# YYB-Sheet1.net
KiCad netlist of a schematic drawn in Altium Designer
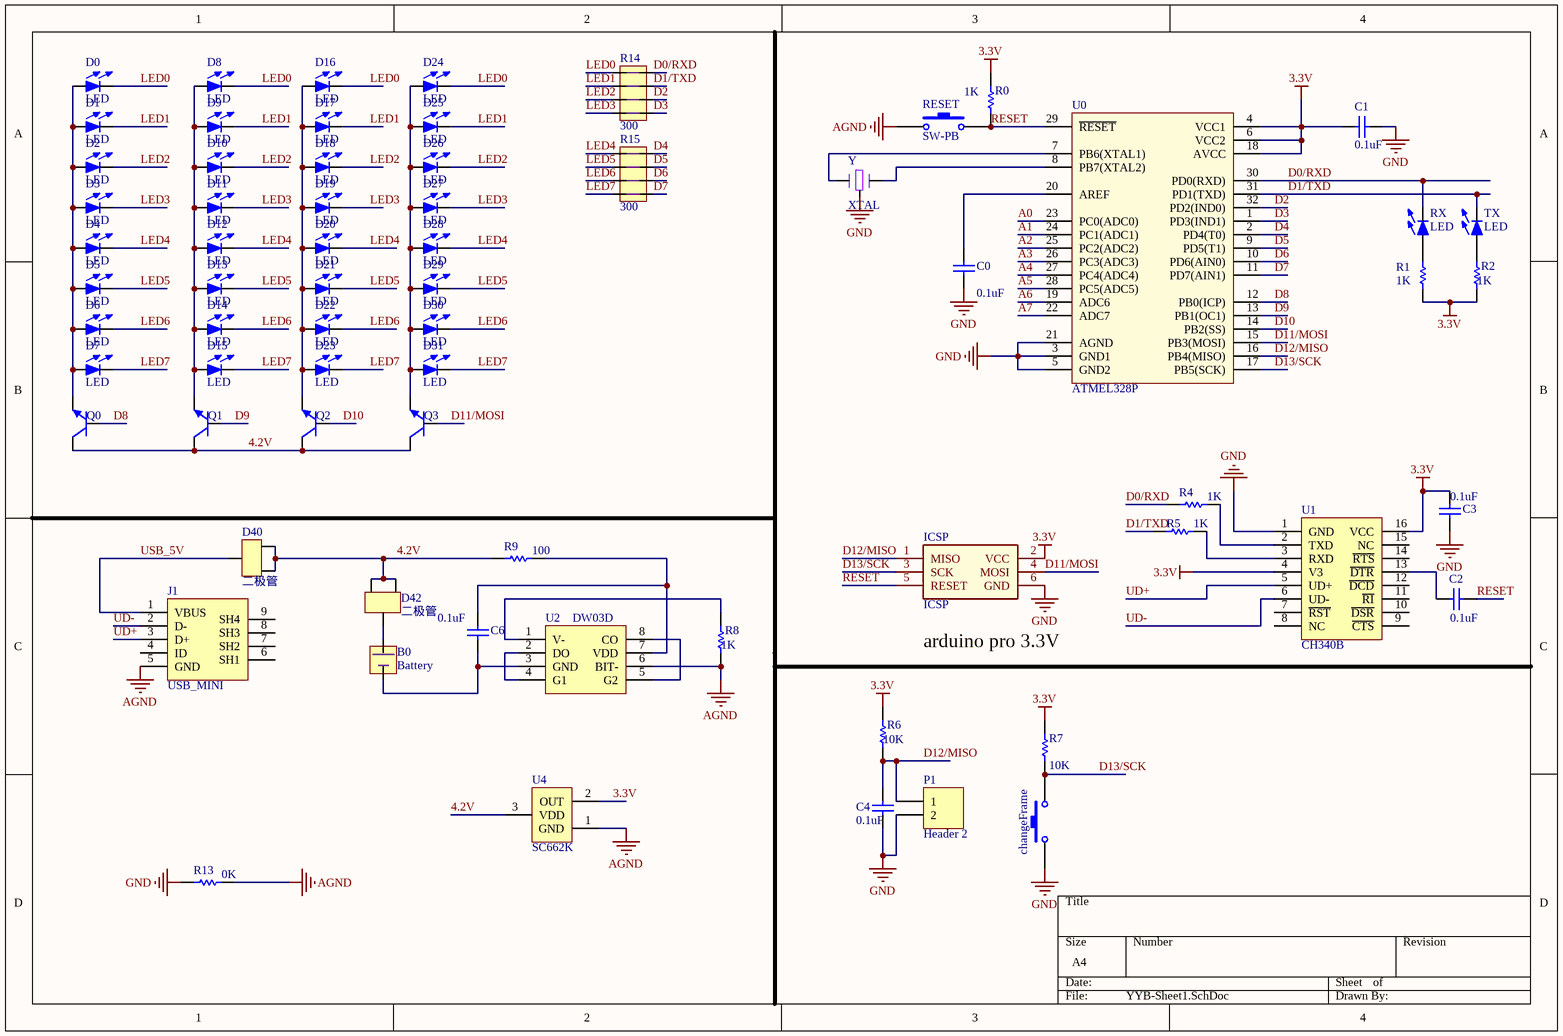
[diagram p0: YYB-Sheet1.SchDoc]

(export (version "E")
  (design (tool "Eeschema 10.0.6"))
  (components
    (comp (ref "B0") (value "Battery") (footprint "LI") (libsource (lib "aistlab") (part "Battery")))
    (comp (ref "C0")
      (value "0.1uF")
      (footprint "6-0805_N")
      (description "Capacitor")
      (fields (field (name "PUBLISHER") "Altium Limited"))
      (libsource (lib "Miscellaneous Devices") (part "Cap"))
    )
    (comp (ref "C1")
      (value "0.1uF")
      (footprint "6-0805_N")
      (description "Capacitor")
      (fields (field (name "Comment") "Cap") (field (name "PUBLISHER") "Altium Limited"))
      (libsource (lib "Miscellaneous Devices") (part "Cap"))
    )
    (comp (ref "C2")
      (value "0.1uF")
      (footprint "6-0805_N")
      (description "Capacitor")
      (fields (field (name "Comment") "Cap") (field (name "PUBLISHER") "Altium Limited"))
      (libsource (lib "Miscellaneous Devices") (part "Cap"))
    )
    (comp (ref "C3")
      (value "0.1uF")
      (footprint "6-0805_N")
      (description "Capacitor")
      (fields (field (name "Comment") "Cap") (field (name "PUBLISHER") "Altium Limited"))
      (libsource (lib "Miscellaneous Devices") (part "Cap"))
    )
    (comp (ref "C4")
      (value "0.1uF")
      (footprint "6-0805_N")
      (description "Capacitor")
      (fields (field (name "Comment") "Cap") (field (name "PUBLISHER") "Altium Limited"))
      (libsource (lib "Miscellaneous Devices") (part "Cap"))
    )
    (comp (ref "C6")
      (value "0.1uF")
      (footprint "6-0805_N")
      (description "Capacitor")
      (fields (field (name "Comment") "Cap") (field (name "PUBLISHER") "Altium Limited"))
      (libsource (lib "Miscellaneous Devices") (part "Cap"))
    )
    (comp (ref "changeFrame")
      (value "SW-PB")
      (footprint "KEY_SODFL_2-Leads")
      (description "Switch")
      (fields (field (name "PUBLISHER") "Altium Limited"))
      (libsource (lib "Miscellaneous Devices") (part "SW-PB"))
    )
    (comp (ref "D0") (value "LED") (footprint "LED_0805") (libsource (lib "aistlab") (part "LED")))
    (comp (ref "D1") (value "LED") (footprint "LED_0805") (libsource (lib "aistlab") (part "LED")))
    (comp (ref "D2") (value "LED") (footprint "LED_0805") (libsource (lib "aistlab") (part "LED")))
    (comp (ref "D3") (value "LED") (footprint "LED_0805") (libsource (lib "aistlab") (part "LED")))
    (comp (ref "D4") (value "LED") (footprint "LED_0805") (libsource (lib "aistlab") (part "LED")))
    (comp (ref "D5") (value "LED") (footprint "LED_0805") (libsource (lib "aistlab") (part "LED")))
    (comp (ref "D6") (value "LED") (footprint "LED_0805") (libsource (lib "aistlab") (part "LED")))
    (comp (ref "D7") (value "LED") (footprint "LED_0805") (libsource (lib "aistlab") (part "LED")))
    (comp (ref "D8") (value "LED") (footprint "LED_0805") (libsource (lib "aistlab") (part "LED")))
    (comp (ref "D9") (value "LED") (footprint "LED_0805") (libsource (lib "aistlab") (part "LED")))
    (comp (ref "D10") (value "LED") (footprint "LED_0805") (libsource (lib "aistlab") (part "LED")))
    (comp (ref "D11") (value "LED") (footprint "LED_0805") (libsource (lib "aistlab") (part "LED")))
    (comp (ref "D12") (value "LED") (footprint "LED_0805") (libsource (lib "aistlab") (part "LED")))
    (comp (ref "D13") (value "LED") (footprint "LED_0805") (libsource (lib "aistlab") (part "LED")))
    (comp (ref "D14") (value "LED") (footprint "LED_0805") (libsource (lib "aistlab") (part "LED")))
    (comp (ref "D15") (value "LED") (footprint "LED_0805") (libsource (lib "aistlab") (part "LED")))
    (comp (ref "D16") (value "LED") (footprint "LED_0805") (libsource (lib "aistlab") (part "LED")))
    (comp (ref "D17") (value "LED") (footprint "LED_0805") (libsource (lib "aistlab") (part "LED")))
    (comp (ref "D18") (value "LED") (footprint "LED_0805") (libsource (lib "aistlab") (part "LED")))
    (comp (ref "D19") (value "LED") (footprint "LED_0805") (libsource (lib "aistlab") (part "LED")))
    (comp (ref "D20") (value "LED") (footprint "LED_0805") (libsource (lib "aistlab") (part "LED")))
    (comp (ref "D21") (value "LED") (footprint "LED_0805") (libsource (lib "aistlab") (part "LED")))
    (comp (ref "D22") (value "LED") (footprint "LED_0805") (libsource (lib "aistlab") (part "LED")))
    (comp (ref "D23") (value "LED") (footprint "LED_0805") (libsource (lib "aistlab") (part "LED")))
    (comp (ref "D24") (value "LED") (footprint "LED_0805") (libsource (lib "aistlab") (part "LED")))
    (comp (ref "D25") (value "LED") (footprint "LED_0805") (libsource (lib "aistlab") (part "LED")))
    (comp (ref "D26") (value "LED") (footprint "LED_0805") (libsource (lib "aistlab") (part "LED")))
    (comp (ref "D27") (value "LED") (footprint "LED_0805") (libsource (lib "aistlab") (part "LED")))
    (comp (ref "D28") (value "LED") (footprint "LED_0805") (libsource (lib "aistlab") (part "LED")))
    (comp (ref "D29") (value "LED") (footprint "LED_0805") (libsource (lib "aistlab") (part "LED")))
    (comp (ref "D30") (value "LED") (footprint "LED_0805") (libsource (lib "aistlab") (part "LED")))
    (comp (ref "D31") (value "LED") (footprint "LED_0805") (libsource (lib "aistlab") (part "LED")))
    (comp (ref "D40") (value "二极管") (footprint "SOT-23") (libsource (lib "aistlab") (part "二极管")))
    (comp (ref "D42") (value "二极管") (footprint "SOT-23") (libsource (lib "") (part "二极管_1")))
    (comp (ref "ICSP") (value "ICSP") (footprint "DIP6") (libsource (lib "aistlab") (part "ICSP")))
    (comp (ref "J1")
      (value "USB_MINI")
      (footprint "MICRO_USB")
      (libsource (lib "YYB-Schlib1") (part "USB_MINI"))
    )
    (comp (ref "P1")
      (value "Header 2")
      (footprint "HDR1X2")
      (description "Header, 2-Pin")
      (fields (field (name "PUBLISHER") "Altium Limited"))
      (libsource (lib "Miscellaneous Connectors") (part "Header 2"))
    )
    (comp (ref "Q0")
      (value "transistor")
      (footprint "SOT-23")
      (libsource (lib "aistlab") (part "transistor"))
    )
    (comp (ref "Q1")
      (value "transistor")
      (footprint "SOT-23")
      (libsource (lib "aistlab") (part "transistor"))
    )
    (comp (ref "Q2")
      (value "transistor")
      (footprint "SOT-23")
      (libsource (lib "aistlab") (part "transistor"))
    )
    (comp (ref "Q3")
      (value "transistor")
      (footprint "SOT-23")
      (libsource (lib "aistlab") (part "transistor"))
    )
    (comp (ref "R0")
      (value "1K")
      (footprint "6-0805_N")
      (description "Resistor")
      (fields (field (name "PUBLISHER") "Altium Limited"))
      (libsource (lib "Miscellaneous Devices") (part "Res1"))
    )
    (comp (ref "R1")
      (value "1K")
      (footprint "6-0805_N")
      (description "Resistor")
      (fields (field (name "Comment") "Res1") (field (name "PUBLISHER") "Altium Limited"))
      (libsource (lib "Miscellaneous Devices") (part "Res1"))
    )
    (comp (ref "R2")
      (value "1K")
      (footprint "6-0805_N")
      (description "Resistor")
      (fields (field (name "Comment") "Res1") (field (name "PUBLISHER") "Altium Limited"))
      (libsource (lib "Miscellaneous Devices") (part "Res1"))
    )
    (comp (ref "R4")
      (value "1K")
      (footprint "6-0805_N")
      (description "Resistor")
      (fields (field (name "Comment") "Res1") (field (name "PUBLISHER") "Altium Limited"))
      (libsource (lib "Miscellaneous Devices") (part "Res1"))
    )
    (comp (ref "R5")
      (value "1K")
      (footprint "6-0805_N")
      (description "Resistor")
      (fields (field (name "Comment") "Res1") (field (name "PUBLISHER") "Altium Limited"))
      (libsource (lib "Miscellaneous Devices") (part "Res1"))
    )
    (comp (ref "R6")
      (value "10K")
      (footprint "6-0805_N")
      (description "Resistor")
      (fields (field (name "Comment") "Res1") (field (name "PUBLISHER") "Altium Limited"))
      (libsource (lib "Miscellaneous Devices") (part "Res1"))
    )
    (comp (ref "R7")
      (value "10K")
      (footprint "6-0805_N")
      (description "Resistor")
      (fields (field (name "Comment") "Res1") (field (name "PUBLISHER") "Altium Limited"))
      (libsource (lib "Miscellaneous Devices") (part "Res1"))
    )
    (comp (ref "R8")
      (value "1K")
      (footprint "6-0805_N")
      (description "Resistor")
      (fields (field (name "Comment") "Res1") (field (name "PUBLISHER") "Altium Limited"))
      (libsource (lib "Miscellaneous Devices") (part "Res1"))
    )
    (comp (ref "R9")
      (value "100")
      (footprint "6-0805_N")
      (description "Resistor")
      (fields (field (name "Comment") "Res1") (field (name "PUBLISHER") "Altium Limited"))
      (libsource (lib "Miscellaneous Devices") (part "Res1"))
    )
    (comp (ref "R13")
      (value "0K")
      (footprint "6-0805_N")
      (description "Resistor")
      (fields (field (name "Comment") "Res1") (field (name "PUBLISHER") "Altium Limited"))
      (libsource (lib "Miscellaneous Devices") (part "Res1"))
    )
    (comp (ref "R14") (value "300") (footprint "0402_Rx4") (libsource (lib "") (part "ResistorPacks_1")))
    (comp (ref "R15") (value "300") (footprint "0402_Rx4") (libsource (lib "aistlab") (part "ResistorPacks")))
    (comp (ref "RESET")
      (value "SW-PB")
      (footprint "KEY_SODFL_2-Leads")
      (description "Switch")
      (fields (field (name "PUBLISHER") "Altium Limited"))
      (libsource (lib "Miscellaneous Devices") (part "SW-PB"))
    )
    (comp (ref "RX") (value "LED") (footprint "LED_0805") (libsource (lib "aistlab") (part "LED")))
    (comp (ref "TX") (value "LED") (footprint "LED_0805") (libsource (lib "aistlab") (part "LED")))
    (comp (ref "U0")
      (value "ATMEL328P")
      (footprint "Atmel 328p 5*5")
      (libsource (lib "aistlab") (part "ATMEL-328P"))
    )
    (comp (ref "U1")
      (value "CH340B")
      (footprint "SOP16")
      (description "usb to uart")
      (libsource (lib "aistlab") (part "CH340B"))
    )
    (comp (ref "U2") (value "DW03D") (footprint "SOP-8") (libsource (lib "aistlab") (part "DW03D")))
    (comp (ref "U4")
      (value "SC662K")
      (footprint "SOT-23")
      (description "3.3V 稳压芯片")
      (libsource (lib "aistlab") (part "SC662k-3.3V"))
    )
    (comp (ref "Y") (value "XTAL") (footprint "XTAL") (libsource (lib "aistlab") (part "XTAL")))
  )
  (nets
    (net (code "1") (name "/4.2V") (class "Default")
      (node (ref "D40") (pin "1") (pinfunction "1_1") (pintype "passive"))
      (node (ref "D40") (pin "2") (pinfunction "2_2") (pintype "passive"))
      (node (ref "D42") (pin "1") (pinfunction "1_1") (pintype "passive"))
      (node (ref "D42") (pin "2") (pinfunction "2_2") (pintype "passive"))
      (node (ref "Q0") (pin "3") (pinfunction "C_3") (pintype "passive"))
      (node (ref "Q1") (pin "3") (pinfunction "C_3") (pintype "passive"))
      (node (ref "Q2") (pin "3") (pinfunction "C_3") (pintype "passive"))
      (node (ref "Q3") (pin "3") (pinfunction "C_3") (pintype "passive"))
      (node (ref "R9") (pin "1") (pinfunction "1_1") (pintype "passive"))
      (node (ref "U4") (pin "3") (pinfunction "VDD_3") (pintype "passive"))
    )
    (net (code "2") (name "/A0") (class "Default")
      (node (ref "U0") (pin "23") (pinfunction "PC0(ADC0)_23") (pintype "open_collector"))
    )
    (net (code "3") (name "/A1") (class "Default")
      (node (ref "U0") (pin "24") (pinfunction "PC1(ADC1)_24") (pintype "open_collector"))
    )
    (net (code "4") (name "/A2") (class "Default")
      (node (ref "U0") (pin "25") (pinfunction "PC2(ADC2)_25") (pintype "open_collector"))
    )
    (net (code "5") (name "/A3") (class "Default")
      (node (ref "U0") (pin "26") (pinfunction "PC3(ADC3)_26") (pintype "open_collector"))
    )
    (net (code "6") (name "/A4") (class "Default")
      (node (ref "U0") (pin "27") (pinfunction "PC4(ADC4)_27") (pintype "open_collector"))
    )
    (net (code "7") (name "/A5") (class "Default")
      (node (ref "U0") (pin "28") (pinfunction "PC5(ADC5)_28") (pintype "open_collector"))
    )
    (net (code "8") (name "/A6") (class "Default")
      (node (ref "U0") (pin "19") (pinfunction "ADC6_19") (pintype "open_collector"))
    )
    (net (code "9") (name "/A7") (class "Default")
      (node (ref "U0") (pin "22") (pinfunction "ADC7_22") (pintype "open_collector"))
    )
    (net (code "10") (name "/D0{slash}RXD") (class "Default")
      (node (ref "R14") (pin "4") (pinfunction "4_4") (pintype "passive"))
      (node (ref "R4") (pin "1") (pinfunction "1_1") (pintype "passive"))
      (node (ref "RX") (pin "2") (pinfunction "2_2") (pintype "passive"))
      (node (ref "U0") (pin "30") (pinfunction "PD0(RXD)_30") (pintype "open_collector"))
    )
    (net (code "11") (name "/D1{slash}TXD") (class "Default")
      (node (ref "R14") (pin "3") (pinfunction "3_3") (pintype "passive"))
      (node (ref "R5") (pin "1") (pinfunction "1_1") (pintype "passive"))
      (node (ref "TX") (pin "2") (pinfunction "2_2") (pintype "passive"))
      (node (ref "U0") (pin "31") (pinfunction "PD1(TXD)_31") (pintype "open_collector"))
    )
    (net (code "12") (name "/D2") (class "Default")
      (node (ref "R14") (pin "2") (pinfunction "2_2") (pintype "passive"))
      (node (ref "U0") (pin "32") (pinfunction "PD2(IND0)_32") (pintype "open_collector"))
    )
    (net (code "13") (name "/D3") (class "Default")
      (node (ref "R14") (pin "1") (pinfunction "1_1") (pintype "passive"))
      (node (ref "U0") (pin "1") (pinfunction "PD3(IND1)_1") (pintype "open_collector"))
    )
    (net (code "14") (name "/D4") (class "Default")
      (node (ref "R15") (pin "8") (pinfunction "8_8") (pintype "passive"))
      (node (ref "U0") (pin "2") (pinfunction "PD4(T0)_2") (pintype "open_collector"))
    )
    (net (code "15") (name "/D5") (class "Default")
      (node (ref "R15") (pin "7") (pinfunction "7_7") (pintype "passive"))
      (node (ref "U0") (pin "9") (pinfunction "PD5(T1)_9") (pintype "open_collector"))
    )
    (net (code "16") (name "/D6") (class "Default")
      (node (ref "R15") (pin "6") (pinfunction "6_6") (pintype "passive"))
      (node (ref "U0") (pin "10") (pinfunction "PD6(AIN0)_10") (pintype "open_collector"))
    )
    (net (code "17") (name "/D7") (class "Default")
      (node (ref "R15") (pin "5") (pinfunction "5_5") (pintype "passive"))
      (node (ref "U0") (pin "11") (pinfunction "PD7(AIN1)_11") (pintype "open_collector"))
    )
    (net (code "18") (name "/D8") (class "Default")
      (node (ref "Q0") (pin "1") (pinfunction "B_1") (pintype "passive"))
      (node (ref "U0") (pin "12") (pinfunction "PB0(ICP)_12") (pintype "open_collector"))
    )
    (net (code "19") (name "/D9") (class "Default")
      (node (ref "Q1") (pin "1") (pinfunction "B_1") (pintype "passive"))
      (node (ref "U0") (pin "13") (pinfunction "PB1(OC1)_13") (pintype "open_collector"))
    )
    (net (code "20") (name "/D10") (class "Default")
      (node (ref "Q2") (pin "1") (pinfunction "B_1") (pintype "passive"))
      (node (ref "U0") (pin "14") (pinfunction "PB2(SS)_14") (pintype "open_collector"))
    )
    (net (code "21") (name "/D11{slash}MOSI") (class "Default")
      (node (ref "ICSP") (pin "4") (pinfunction "MOSI_4") (pintype "open_collector"))
      (node (ref "Q3") (pin "1") (pinfunction "B_1") (pintype "passive"))
      (node (ref "U0") (pin "15") (pinfunction "PB3(MOSI)_15") (pintype "open_collector"))
    )
    (net (code "22") (name "/D12{slash}MISO") (class "Default")
      (node (ref "C4") (pin "2") (pinfunction "2_2") (pintype "passive"))
      (node (ref "ICSP") (pin "1") (pinfunction "MISO_1") (pintype "open_collector"))
      (node (ref "P1") (pin "1") (pinfunction "1_1") (pintype "passive"))
      (node (ref "R6") (pin "1") (pinfunction "1_1") (pintype "passive"))
      (node (ref "U0") (pin "16") (pinfunction "PB4(MISO)_16") (pintype "open_collector"))
    )
    (net (code "23") (name "/D13{slash}SCK") (class "Default")
      (node (ref "ICSP") (pin "3") (pinfunction "SCK_3") (pintype "open_collector"))
      (node (ref "R7") (pin "1") (pinfunction "1_1") (pintype "passive"))
      (node (ref "U0") (pin "17") (pinfunction "PB5(SCK)_17") (pintype "open_collector"))
      (node (ref "changeFrame") (pin "2") (pinfunction "2_2") (pintype "passive"))
    )
    (net (code "24") (name "/LED0") (class "Default")
      (node (ref "D0") (pin "2") (pinfunction "2_2") (pintype "passive"))
      (node (ref "D16") (pin "2") (pinfunction "2_2") (pintype "passive"))
      (node (ref "D24") (pin "2") (pinfunction "2_2") (pintype "passive"))
      (node (ref "D8") (pin "2") (pinfunction "2_2") (pintype "passive"))
      (node (ref "R14") (pin "5") (pinfunction "5_5") (pintype "passive"))
    )
    (net (code "25") (name "/LED1") (class "Default")
      (node (ref "D1") (pin "2") (pinfunction "2_2") (pintype "passive"))
      (node (ref "D17") (pin "2") (pinfunction "2_2") (pintype "passive"))
      (node (ref "D25") (pin "2") (pinfunction "2_2") (pintype "passive"))
      (node (ref "D9") (pin "2") (pinfunction "2_2") (pintype "passive"))
      (node (ref "R14") (pin "6") (pinfunction "6_6") (pintype "passive"))
    )
    (net (code "26") (name "/LED2") (class "Default")
      (node (ref "D10") (pin "2") (pinfunction "2_2") (pintype "passive"))
      (node (ref "D18") (pin "2") (pinfunction "2_2") (pintype "passive"))
      (node (ref "D2") (pin "2") (pinfunction "2_2") (pintype "passive"))
      (node (ref "D26") (pin "2") (pinfunction "2_2") (pintype "passive"))
      (node (ref "R14") (pin "7") (pinfunction "7_7") (pintype "passive"))
    )
    (net (code "27") (name "/LED3") (class "Default")
      (node (ref "D11") (pin "2") (pinfunction "2_2") (pintype "passive"))
      (node (ref "D19") (pin "2") (pinfunction "2_2") (pintype "passive"))
      (node (ref "D27") (pin "2") (pinfunction "2_2") (pintype "passive"))
      (node (ref "D3") (pin "2") (pinfunction "2_2") (pintype "passive"))
      (node (ref "R14") (pin "8") (pinfunction "8_8") (pintype "passive"))
    )
    (net (code "28") (name "/LED4") (class "Default")
      (node (ref "D12") (pin "2") (pinfunction "2_2") (pintype "passive"))
      (node (ref "D20") (pin "2") (pinfunction "2_2") (pintype "passive"))
      (node (ref "D28") (pin "2") (pinfunction "2_2") (pintype "passive"))
      (node (ref "D4") (pin "2") (pinfunction "2_2") (pintype "passive"))
      (node (ref "R15") (pin "1") (pinfunction "1_1") (pintype "passive"))
    )
    (net (code "29") (name "/LED5") (class "Default")
      (node (ref "D13") (pin "2") (pinfunction "2_2") (pintype "passive"))
      (node (ref "D21") (pin "2") (pinfunction "2_2") (pintype "passive"))
      (node (ref "D29") (pin "2") (pinfunction "2_2") (pintype "passive"))
      (node (ref "D5") (pin "2") (pinfunction "2_2") (pintype "passive"))
      (node (ref "R15") (pin "2") (pinfunction "2_2") (pintype "passive"))
    )
    (net (code "30") (name "/LED6") (class "Default")
      (node (ref "D14") (pin "2") (pinfunction "2_2") (pintype "passive"))
      (node (ref "D22") (pin "2") (pinfunction "2_2") (pintype "passive"))
      (node (ref "D30") (pin "2") (pinfunction "2_2") (pintype "passive"))
      (node (ref "D6") (pin "2") (pinfunction "2_2") (pintype "passive"))
      (node (ref "R15") (pin "3") (pinfunction "3_3") (pintype "passive"))
    )
    (net (code "31") (name "/LED7") (class "Default")
      (node (ref "D15") (pin "2") (pinfunction "2_2") (pintype "passive"))
      (node (ref "D23") (pin "2") (pinfunction "2_2") (pintype "passive"))
      (node (ref "D31") (pin "2") (pinfunction "2_2") (pintype "passive"))
      (node (ref "D7") (pin "2") (pinfunction "2_2") (pintype "passive"))
      (node (ref "R15") (pin "4") (pinfunction "4_4") (pintype "passive"))
    )
    (net (code "32") (name "/RESET") (class "Default")
      (node (ref "C2") (pin "2") (pinfunction "2_2") (pintype "passive"))
      (node (ref "ICSP") (pin "5") (pinfunction "RESET_5") (pintype "open_collector"))
      (node (ref "R0") (pin "2") (pinfunction "2_2") (pintype "passive"))
      (node (ref "RESET") (pin "2") (pinfunction "2_2") (pintype "passive"))
      (node (ref "U0") (pin "29") (pinfunction "~{RESET}_29") (pintype "open_collector"))
    )
    (net (code "33") (name "/UD+") (class "Default")
      (node (ref "J1") (pin "3") (pinfunction "D+_3") (pintype "passive"))
      (node (ref "U1") (pin "5") (pinfunction "UD+_5") (pintype "open_collector"))
    )
    (net (code "34") (name "/UD-") (class "Default")
      (node (ref "J1") (pin "2") (pinfunction "D-_2") (pintype "passive"))
      (node (ref "U1") (pin "6") (pinfunction "UD-_6") (pintype "open_collector"))
    )
    (net (code "35") (name "/USB_5V") (class "Default")
      (node (ref "D40") (pin "3") (pinfunction "3_3") (pintype "passive"))
      (node (ref "J1") (pin "1") (pinfunction "VBUS_1") (pintype "passive"))
    )
    (net (code "36") (name "3.3V") (class "Default")
      (node (ref "C1") (pin "2") (pinfunction "2_2") (pintype "passive"))
      (node (ref "C3") (pin "2") (pinfunction "2_2") (pintype "passive"))
      (node (ref "ICSP") (pin "2") (pinfunction "VCC_2") (pintype "passive"))
      (node (ref "R0") (pin "1") (pinfunction "1_1") (pintype "passive"))
      (node (ref "R1") (pin "1") (pinfunction "1_1") (pintype "passive"))
      (node (ref "R2") (pin "1") (pinfunction "1_1") (pintype "passive"))
      (node (ref "R6") (pin "2") (pinfunction "2_2") (pintype "passive"))
      (node (ref "R7") (pin "2") (pinfunction "2_2") (pintype "passive"))
      (node (ref "U0") (pin "18") (pinfunction "AVCC_18") (pintype "power_in"))
      (node (ref "U0") (pin "4") (pinfunction "VCC1_4") (pintype "power_in"))
      (node (ref "U0") (pin "6") (pinfunction "VCC2_6") (pintype "power_in"))
      (node (ref "U1") (pin "16") (pinfunction "VCC_16") (pintype "power_in"))
      (node (ref "U1") (pin "4") (pinfunction "V3_4") (pintype "power_in"))
      (node (ref "U4") (pin "2") (pinfunction "OUT_2") (pintype "passive"))
    )
    (net (code "37") (name "AGND") (class "Default")
      (node (ref "J1") (pin "5") (pinfunction "GND_5") (pintype "passive"))
      (node (ref "R13") (pin "2") (pinfunction "2_2") (pintype "passive"))
      (node (ref "R8") (pin "1") (pinfunction "1_1") (pintype "passive"))
      (node (ref "RESET") (pin "1") (pinfunction "1_1") (pintype "passive"))
      (node (ref "U2") (pin "6") (pinfunction "BIT-_6") (pintype "passive"))
      (node (ref "U4") (pin "1") (pinfunction "GND_1") (pintype "open_collector"))
    )
    (net (code "38") (name "GND") (class "Default")
      (node (ref "C0") (pin "1") (pinfunction "1_1") (pintype "passive"))
      (node (ref "C1") (pin "1") (pinfunction "1_1") (pintype "passive"))
      (node (ref "C3") (pin "1") (pinfunction "1_1") (pintype "passive"))
      (node (ref "C4") (pin "1") (pinfunction "1_1") (pintype "passive"))
      (node (ref "ICSP") (pin "6") (pinfunction "GND_6") (pintype "open_collector"))
      (node (ref "P1") (pin "2") (pinfunction "2_2") (pintype "passive"))
      (node (ref "R13") (pin "1") (pinfunction "1_1") (pintype "passive"))
      (node (ref "U0") (pin "21") (pinfunction "AGND_21") (pintype "open_collector"))
      (node (ref "U0") (pin "3") (pinfunction "GND1_3") (pintype "open_collector"))
      (node (ref "U0") (pin "5") (pinfunction "GND2_5") (pintype "open_collector"))
      (node (ref "U1") (pin "1") (pinfunction "GND_1") (pintype "open_collector"))
      (node (ref "Y") (pin "2") (pinfunction "2_2") (pintype "passive"))
      (node (ref "changeFrame") (pin "1") (pinfunction "1_1") (pintype "passive"))
    )
    (net (code "39") (name "Net-(B0-+)") (class "Default")
      (node (ref "B0") (pin "1") (pinfunction "+_1") (pintype "passive"))
      (node (ref "D42") (pin "3") (pinfunction "3_3") (pintype "passive"))
    )
    (net (code "40") (name "Net-(Q0-E)") (class "Default")
      (node (ref "D0") (pin "1") (pinfunction "1_1") (pintype "passive"))
      (node (ref "D1") (pin "1") (pinfunction "1_1") (pintype "passive"))
      (node (ref "D2") (pin "1") (pinfunction "1_1") (pintype "passive"))
      (node (ref "D3") (pin "1") (pinfunction "1_1") (pintype "passive"))
      (node (ref "D4") (pin "1") (pinfunction "1_1") (pintype "passive"))
      (node (ref "D5") (pin "1") (pinfunction "1_1") (pintype "passive"))
      (node (ref "D6") (pin "1") (pinfunction "1_1") (pintype "passive"))
      (node (ref "D7") (pin "1") (pinfunction "1_1") (pintype "passive"))
      (node (ref "Q0") (pin "2") (pinfunction "E_2") (pintype "passive"))
    )
    (net (code "41") (name "Net-(Q1-E)") (class "Default")
      (node (ref "D10") (pin "1") (pinfunction "1_1") (pintype "passive"))
      (node (ref "D11") (pin "1") (pinfunction "1_1") (pintype "passive"))
      (node (ref "D12") (pin "1") (pinfunction "1_1") (pintype "passive"))
      (node (ref "D13") (pin "1") (pinfunction "1_1") (pintype "passive"))
      (node (ref "D14") (pin "1") (pinfunction "1_1") (pintype "passive"))
      (node (ref "D15") (pin "1") (pinfunction "1_1") (pintype "passive"))
      (node (ref "D8") (pin "1") (pinfunction "1_1") (pintype "passive"))
      (node (ref "D9") (pin "1") (pinfunction "1_1") (pintype "passive"))
      (node (ref "Q1") (pin "2") (pinfunction "E_2") (pintype "passive"))
    )
    (net (code "42") (name "Net-(Q2-E)") (class "Default")
      (node (ref "D16") (pin "1") (pinfunction "1_1") (pintype "passive"))
      (node (ref "D17") (pin "1") (pinfunction "1_1") (pintype "passive"))
      (node (ref "D18") (pin "1") (pinfunction "1_1") (pintype "passive"))
      (node (ref "D19") (pin "1") (pinfunction "1_1") (pintype "passive"))
      (node (ref "D20") (pin "1") (pinfunction "1_1") (pintype "passive"))
      (node (ref "D21") (pin "1") (pinfunction "1_1") (pintype "passive"))
      (node (ref "D22") (pin "1") (pinfunction "1_1") (pintype "passive"))
      (node (ref "D23") (pin "1") (pinfunction "1_1") (pintype "passive"))
      (node (ref "Q2") (pin "2") (pinfunction "E_2") (pintype "passive"))
    )
    (net (code "43") (name "Net-(Q3-E)") (class "Default")
      (node (ref "D24") (pin "1") (pinfunction "1_1") (pintype "passive"))
      (node (ref "D25") (pin "1") (pinfunction "1_1") (pintype "passive"))
      (node (ref "D26") (pin "1") (pinfunction "1_1") (pintype "passive"))
      (node (ref "D27") (pin "1") (pinfunction "1_1") (pintype "passive"))
      (node (ref "D28") (pin "1") (pinfunction "1_1") (pintype "passive"))
      (node (ref "D29") (pin "1") (pinfunction "1_1") (pintype "passive"))
      (node (ref "D30") (pin "1") (pinfunction "1_1") (pintype "passive"))
      (node (ref "D31") (pin "1") (pinfunction "1_1") (pintype "passive"))
      (node (ref "Q3") (pin "2") (pinfunction "E_2") (pintype "passive"))
    )
    (net (code "44") (name "Net-(R1-Pad2)") (class "Default")
      (node (ref "R1") (pin "2") (pinfunction "2_2") (pintype "passive"))
      (node (ref "RX") (pin "1") (pinfunction "1_1") (pintype "passive"))
    )
    (net (code "45") (name "Net-(R2-Pad2)") (class "Default")
      (node (ref "R2") (pin "2") (pinfunction "2_2") (pintype "passive"))
      (node (ref "TX") (pin "1") (pinfunction "1_1") (pintype "passive"))
    )
    (net (code "46") (name "Net-(U0-AREF)") (class "Default")
      (node (ref "C0") (pin "2") (pinfunction "2_2") (pintype "passive"))
      (node (ref "U0") (pin "20") (pinfunction "AREF_20") (pintype "open_collector"))
    )
    (net (code "47") (name "Net-(U0-PB6(XTAL1))") (class "Default")
      (node (ref "U0") (pin "7") (pinfunction "PB6(XTAL1)_7") (pintype "open_collector"))
      (node (ref "Y") (pin "1") (pinfunction "1_1") (pintype "passive"))
    )
    (net (code "48") (name "Net-(U0-PB7(XTAL2))") (class "Default")
      (node (ref "U0") (pin "8") (pinfunction "PB7(XTAL2)_8") (pintype "open_collector"))
      (node (ref "Y") (pin "3") (pinfunction "3_3") (pintype "passive"))
    )
    (net (code "49") (name "Net-(U1-RXD)") (class "Default")
      (node (ref "R5") (pin "2") (pinfunction "2_2") (pintype "passive"))
      (node (ref "U1") (pin "3") (pinfunction "RXD_3") (pintype "open_collector"))
    )
    (net (code "50") (name "Net-(U1-TXD)") (class "Default")
      (node (ref "R4") (pin "2") (pinfunction "2_2") (pintype "passive"))
      (node (ref "U1") (pin "2") (pinfunction "TXD_2") (pintype "open_collector"))
    )
    (net (code "51") (name "Net-(U1-~{DTR})") (class "Default")
      (node (ref "C2") (pin "1") (pinfunction "1_1") (pintype "passive"))
      (node (ref "U1") (pin "13") (pinfunction "~{DTR}_13") (pintype "open_collector"))
    )
    (net (code "52") (name "Net-(U2-CO)") (class "Default")
      (node (ref "U2") (pin "5") (pinfunction "G2_5") (pintype "passive"))
      (node (ref "U2") (pin "8") (pinfunction "CO_8") (pintype "passive"))
    )
    (net (code "53") (name "Net-(U2-DO)") (class "Default")
      (node (ref "U2") (pin "2") (pinfunction "DO_2") (pintype "passive"))
      (node (ref "U2") (pin "4") (pinfunction "G1_4") (pintype "passive"))
    )
    (net (code "54") (name "Net-(U2-GND)") (class "Default")
      (node (ref "B0") (pin "2") (pinfunction "2_2") (pintype "passive"))
      (node (ref "C6") (pin "1") (pinfunction "1_1") (pintype "passive"))
      (node (ref "U2") (pin "3") (pinfunction "GND_3") (pintype "passive"))
    )
    (net (code "55") (name "Net-(U2-V-)") (class "Default")
      (node (ref "R8") (pin "2") (pinfunction "2_2") (pintype "passive"))
      (node (ref "U2") (pin "1") (pinfunction "V-_1") (pintype "power_in"))
    )
    (net (code "56") (name "Net-(U2-VDD)") (class "Default")
      (node (ref "C6") (pin "2") (pinfunction "2_2") (pintype "passive"))
      (node (ref "R9") (pin "2") (pinfunction "2_2") (pintype "passive"))
      (node (ref "U2") (pin "7") (pinfunction "VDD_7") (pintype "passive"))
    )
    (net (code "57") (name "unconnected-(J1-ID-Pad4)") (class "Default")
      (node (ref "J1") (pin "4") (pinfunction "ID_4") (pintype "passive"))
    )
    (net (code "58") (name "unconnected-(J1-SH1-Pad6)") (class "Default")
      (node (ref "J1") (pin "6") (pinfunction "SH1_6") (pintype "passive"))
    )
    (net (code "59") (name "unconnected-(J1-SH2-Pad7)") (class "Default")
      (node (ref "J1") (pin "7") (pinfunction "SH2_7") (pintype "passive"))
    )
    (net (code "60") (name "unconnected-(J1-SH3-Pad8)") (class "Default")
      (node (ref "J1") (pin "8") (pinfunction "SH3_8") (pintype "passive"))
    )
    (net (code "61") (name "unconnected-(J1-SH4-Pad9)") (class "Default")
      (node (ref "J1") (pin "9") (pinfunction "SH4_9") (pintype "passive"))
    )
    (net (code "62") (name "unconnected-(U1-NC-Pad8)") (class "Default")
      (node (ref "U1") (pin "8") (pinfunction "NC_8") (pintype "passive"))
    )
    (net (code "63") (name "unconnected-(U1-NC-Pad15)") (class "Default")
      (node (ref "U1") (pin "15") (pinfunction "NC_15") (pintype "open_collector"))
    )
    (net (code "64") (name "unconnected-(U1-~{CTS}-Pad9)") (class "Default")
      (node (ref "U1") (pin "9") (pinfunction "~{CTS}_9") (pintype "open_collector"))
    )
    (net (code "65") (name "unconnected-(U1-~{DCD}-Pad12)") (class "Default")
      (node (ref "U1") (pin "12") (pinfunction "~{DCD}_12") (pintype "open_collector"))
    )
    (net (code "66") (name "unconnected-(U1-~{DSR}-Pad10)") (class "Default")
      (node (ref "U1") (pin "10") (pinfunction "~{DSR}_10") (pintype "open_collector"))
    )
    (net (code "67") (name "unconnected-(U1-~{RI}-Pad11)") (class "Default")
      (node (ref "U1") (pin "11") (pinfunction "~{RI}_11") (pintype "open_collector"))
    )
    (net (code "68") (name "unconnected-(U1-~{RST}-Pad7)") (class "Default")
      (node (ref "U1") (pin "7") (pinfunction "~{RST}_7") (pintype "open_collector"))
    )
    (net (code "69") (name "unconnected-(U1-~{RTS}-Pad14)") (class "Default")
      (node (ref "U1") (pin "14") (pinfunction "~{RTS}_14") (pintype "open_collector"))
    )
  )
)
